# schematic.net
KiCad netlist of a schematic drawn in Altium Designer
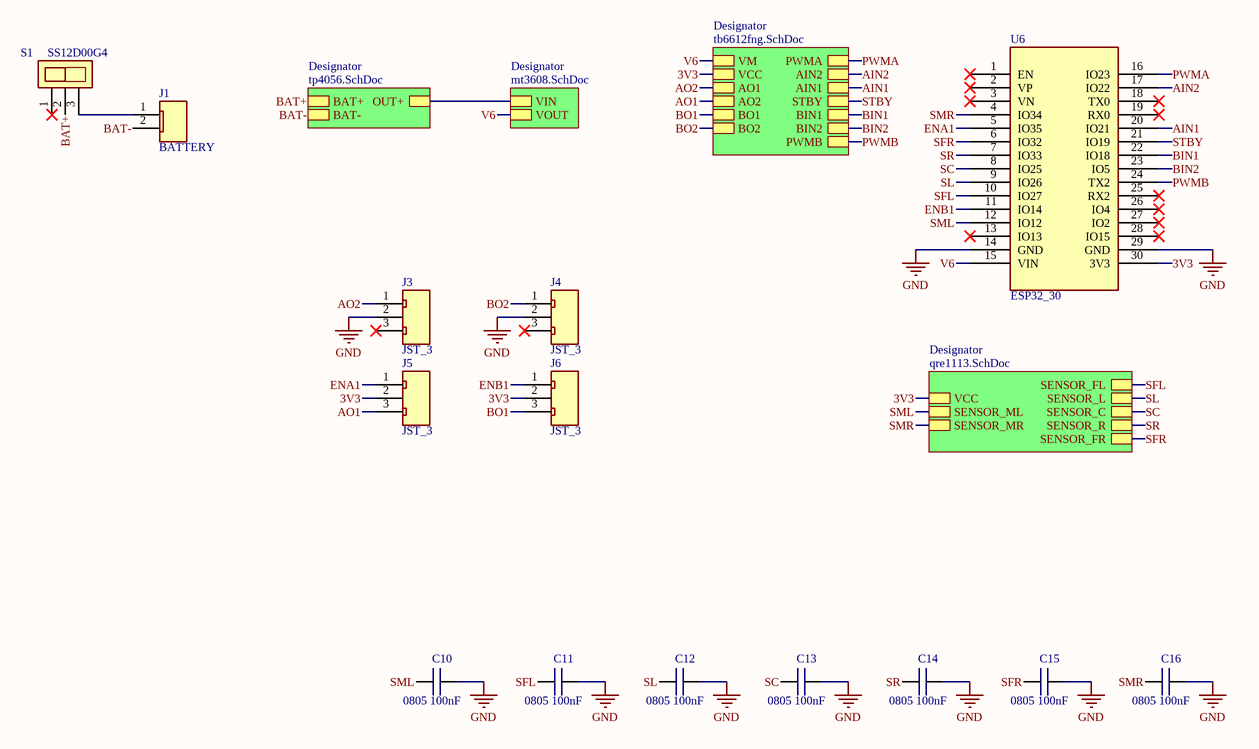
[diagram p0: schematic.SchDoc]

(export (version "E")
  (design (tool "Eeschema 10.0.6"))
  (components
    (comp (ref "C10")
      (value "0805 100nF")
      (footprint "CAPACITOR 0805")
      (libsource (lib "Ceramic Capacitor") (part "CAPACITOR 0805"))
    )
    (comp (ref "C11")
      (value "0805 100nF")
      (footprint "CAPACITOR 0805")
      (libsource (lib "Ceramic Capacitor") (part "CAPACITOR 0805"))
    )
    (comp (ref "C12")
      (value "0805 100nF")
      (footprint "CAPACITOR 0805")
      (libsource (lib "Ceramic Capacitor") (part "CAPACITOR 0805"))
    )
    (comp (ref "C13")
      (value "0805 100nF")
      (footprint "CAPACITOR 0805")
      (libsource (lib "Ceramic Capacitor") (part "CAPACITOR 0805"))
    )
    (comp (ref "C14")
      (value "0805 100nF")
      (footprint "CAPACITOR 0805")
      (libsource (lib "Ceramic Capacitor") (part "CAPACITOR 0805"))
    )
    (comp (ref "C15")
      (value "0805 100nF")
      (footprint "CAPACITOR 0805")
      (libsource (lib "Ceramic Capacitor") (part "CAPACITOR 0805"))
    )
    (comp (ref "C16")
      (value "0805 100nF")
      (footprint "CAPACITOR 0805")
      (libsource (lib "Ceramic Capacitor") (part "CAPACITOR 0805"))
    )
    (comp (ref "J1") (value "BATTERY") (footprint "JST_2") (libsource (lib "Connectors") (part "JST_2")))
    (comp (ref "J3") (value "JST_3") (footprint "JST_3") (libsource (lib "Connectors") (part "JST_3")))
    (comp (ref "J4") (value "JST_3") (footprint "JST_3") (libsource (lib "Connectors") (part "JST_3")))
    (comp (ref "J5") (value "JST_3") (footprint "JST_3") (libsource (lib "Connectors") (part "JST_3")))
    (comp (ref "J6") (value "JST_3") (footprint "JST_3") (libsource (lib "Connectors") (part "JST_3")))
    (comp (ref "S1")
      (value "SS12D00G4")
      (footprint "SS12D00G4")
      (libsource (lib "Buttons & Switches") (part "SS12D00G4"))
    )
    (comp (ref "U6")
      (value "ESP32_30")
      (footprint "ESP32_30")
      (description "Microcontoller Board 30 Pins Wifi 2.4GHz BLE 4.2 ESP32-WROOM-32D")
      (libsource (lib "Espressif Microcontrollers") (part "ESP32_30"))
    )
  )
  (nets
    (net (code "1") (name "/3V3") (class "Default")
      (node (ref "J5") (pin "2") (pintype "passive"))
      (node (ref "J6") (pin "2") (pintype "passive"))
      (node (ref "U6") (pin "30") (pinfunction "3V3_30") (pintype "passive"))
    )
    (net (code "2") (name "/AIN1") (class "Default")
      (node (ref "U6") (pin "20") (pinfunction "IO21_20") (pintype "passive"))
    )
    (net (code "3") (name "/AIN2") (class "Default")
      (node (ref "U6") (pin "17") (pinfunction "IO22_17") (pintype "passive"))
    )
    (net (code "4") (name "/AO1") (class "Default") (node (ref "J5") (pin "3") (pintype "passive")))
    (net (code "5") (name "/AO2") (class "Default") (node (ref "J3") (pin "1") (pintype "passive")))
    (net (code "6") (name "/BAT+") (class "Default") (node (ref "S1") (pin "2") (pintype "passive")))
    (net (code "7") (name "/BAT-") (class "Default") (node (ref "J1") (pin "2") (pintype "passive")))
    (net (code "8") (name "/BIN1") (class "Default")
      (node (ref "U6") (pin "22") (pinfunction "IO18_22") (pintype "passive"))
    )
    (net (code "9") (name "/BIN2") (class "Default")
      (node (ref "U6") (pin "23") (pinfunction "IO5_23") (pintype "passive"))
    )
    (net (code "10") (name "/BO1") (class "Default") (node (ref "J6") (pin "3") (pintype "passive")))
    (net (code "11") (name "/BO2") (class "Default") (node (ref "J4") (pin "1") (pintype "passive")))
    (net (code "12") (name "/ENA1") (class "Default")
      (node (ref "J5") (pin "1") (pintype "passive"))
      (node (ref "U6") (pin "5") (pinfunction "IO35_5") (pintype "passive"))
    )
    (net (code "13") (name "/ENB1") (class "Default")
      (node (ref "J6") (pin "1") (pintype "passive"))
      (node (ref "U6") (pin "11") (pinfunction "IO14_11") (pintype "passive"))
    )
    (net (code "15") (name "/PWMA") (class "Default")
      (node (ref "U6") (pin "16") (pinfunction "IO23_16") (pintype "passive"))
    )
    (net (code "16") (name "/PWMB") (class "Default")
      (node (ref "U6") (pin "24") (pinfunction "TX2_24") (pintype "passive"))
    )
    (net (code "17") (name "/SC") (class "Default")
      (node (ref "C13") (pin "1") (pinfunction "1_1") (pintype "passive"))
      (node (ref "U6") (pin "8") (pinfunction "IO25_8") (pintype "passive"))
    )
    (net (code "18") (name "/SFL") (class "Default")
      (node (ref "C11") (pin "1") (pinfunction "1_1") (pintype "passive"))
      (node (ref "U6") (pin "10") (pinfunction "IO27_10") (pintype "passive"))
    )
    (net (code "19") (name "/SFR") (class "Default")
      (node (ref "C15") (pin "1") (pinfunction "1_1") (pintype "passive"))
      (node (ref "U6") (pin "6") (pinfunction "IO32_6") (pintype "passive"))
    )
    (net (code "20") (name "/SL") (class "Default")
      (node (ref "C12") (pin "1") (pinfunction "1_1") (pintype "passive"))
      (node (ref "U6") (pin "9") (pinfunction "IO26_9") (pintype "passive"))
    )
    (net (code "21") (name "/SML") (class "Default")
      (node (ref "C10") (pin "1") (pinfunction "1_1") (pintype "passive"))
      (node (ref "U6") (pin "12") (pinfunction "IO12_12") (pintype "passive"))
    )
    (net (code "22") (name "/SMR") (class "Default")
      (node (ref "C16") (pin "1") (pinfunction "1_1") (pintype "passive"))
      (node (ref "U6") (pin "4") (pinfunction "IO34_4") (pintype "passive"))
    )
    (net (code "23") (name "/SR") (class "Default")
      (node (ref "C14") (pin "1") (pinfunction "1_1") (pintype "passive"))
      (node (ref "U6") (pin "7") (pinfunction "IO33_7") (pintype "passive"))
    )
    (net (code "24") (name "/STBY") (class "Default")
      (node (ref "U6") (pin "21") (pinfunction "IO19_21") (pintype "passive"))
    )
    (net (code "25") (name "/V6") (class "Default")
      (node (ref "U6") (pin "15") (pinfunction "VIN_15") (pintype "passive"))
    )
    (net (code "26") (name "GND") (class "Default")
      (node (ref "C10") (pin "2") (pinfunction "2_2") (pintype "passive"))
      (node (ref "C11") (pin "2") (pinfunction "2_2") (pintype "passive"))
      (node (ref "C12") (pin "2") (pinfunction "2_2") (pintype "passive"))
      (node (ref "C13") (pin "2") (pinfunction "2_2") (pintype "passive"))
      (node (ref "C14") (pin "2") (pinfunction "2_2") (pintype "passive"))
      (node (ref "C15") (pin "2") (pinfunction "2_2") (pintype "passive"))
      (node (ref "C16") (pin "2") (pinfunction "2_2") (pintype "passive"))
      (node (ref "J3") (pin "2") (pintype "passive"))
      (node (ref "J4") (pin "2") (pintype "passive"))
      (node (ref "U6") (pin "14") (pinfunction "GND_14") (pintype "passive"))
      (node (ref "U6") (pin "29") (pinfunction "GND_29") (pintype "passive"))
    )
    (net (code "27") (name "Net-(J1-Pad1)") (class "Default")
      (node (ref "J1") (pin "1") (pintype "passive"))
      (node (ref "S1") (pin "3") (pintype "passive"))
    )
    (net (code "28") (name "unconnected-(J3-Pad3)") (class "Default")
      (node (ref "J3") (pin "3") (pintype "passive+no_connect"))
    )
    (net (code "29") (name "unconnected-(J4-Pad3)") (class "Default")
      (node (ref "J4") (pin "3") (pintype "passive+no_connect"))
    )
    (net (code "30") (name "unconnected-(S1-Pad1)") (class "Default")
      (node (ref "S1") (pin "1") (pintype "passive+no_connect"))
    )
    (net (code "31") (name "unconnected-(U6-EN-Pad1)") (class "Default")
      (node (ref "U6") (pin "1") (pinfunction "EN_1") (pintype "passive+no_connect"))
    )
    (net (code "32") (name "unconnected-(U6-IO2-Pad27)") (class "Default")
      (node (ref "U6") (pin "27") (pinfunction "IO2_27") (pintype "passive+no_connect"))
    )
    (net (code "33") (name "unconnected-(U6-IO4-Pad26)") (class "Default")
      (node (ref "U6") (pin "26") (pinfunction "IO4_26") (pintype "passive+no_connect"))
    )
    (net (code "34") (name "unconnected-(U6-IO13-Pad13)") (class "Default")
      (node (ref "U6") (pin "13") (pinfunction "IO13_13") (pintype "passive+no_connect"))
    )
    (net (code "35") (name "unconnected-(U6-IO15-Pad28)") (class "Default")
      (node (ref "U6") (pin "28") (pinfunction "IO15_28") (pintype "passive+no_connect"))
    )
    (net (code "36") (name "unconnected-(U6-RX0-Pad19)") (class "Default")
      (node (ref "U6") (pin "19") (pinfunction "RX0_19") (pintype "passive+no_connect"))
    )
    (net (code "37") (name "unconnected-(U6-RX2-Pad25)") (class "Default")
      (node (ref "U6") (pin "25") (pinfunction "RX2_25") (pintype "passive+no_connect"))
    )
    (net (code "38") (name "unconnected-(U6-TX0-Pad18)") (class "Default")
      (node (ref "U6") (pin "18") (pinfunction "TX0_18") (pintype "passive+no_connect"))
    )
    (net (code "39") (name "unconnected-(U6-VN-Pad3)") (class "Default")
      (node (ref "U6") (pin "3") (pinfunction "VN_3") (pintype "passive+no_connect"))
    )
    (net (code "40") (name "unconnected-(U6-VP-Pad2)") (class "Default")
      (node (ref "U6") (pin "2") (pinfunction "VP_2") (pintype "passive+no_connect"))
    )
  )
)
